# ukmarsbot-line-sensor-basic.net
KiCad netlist of a schematic drawn in EAGLE
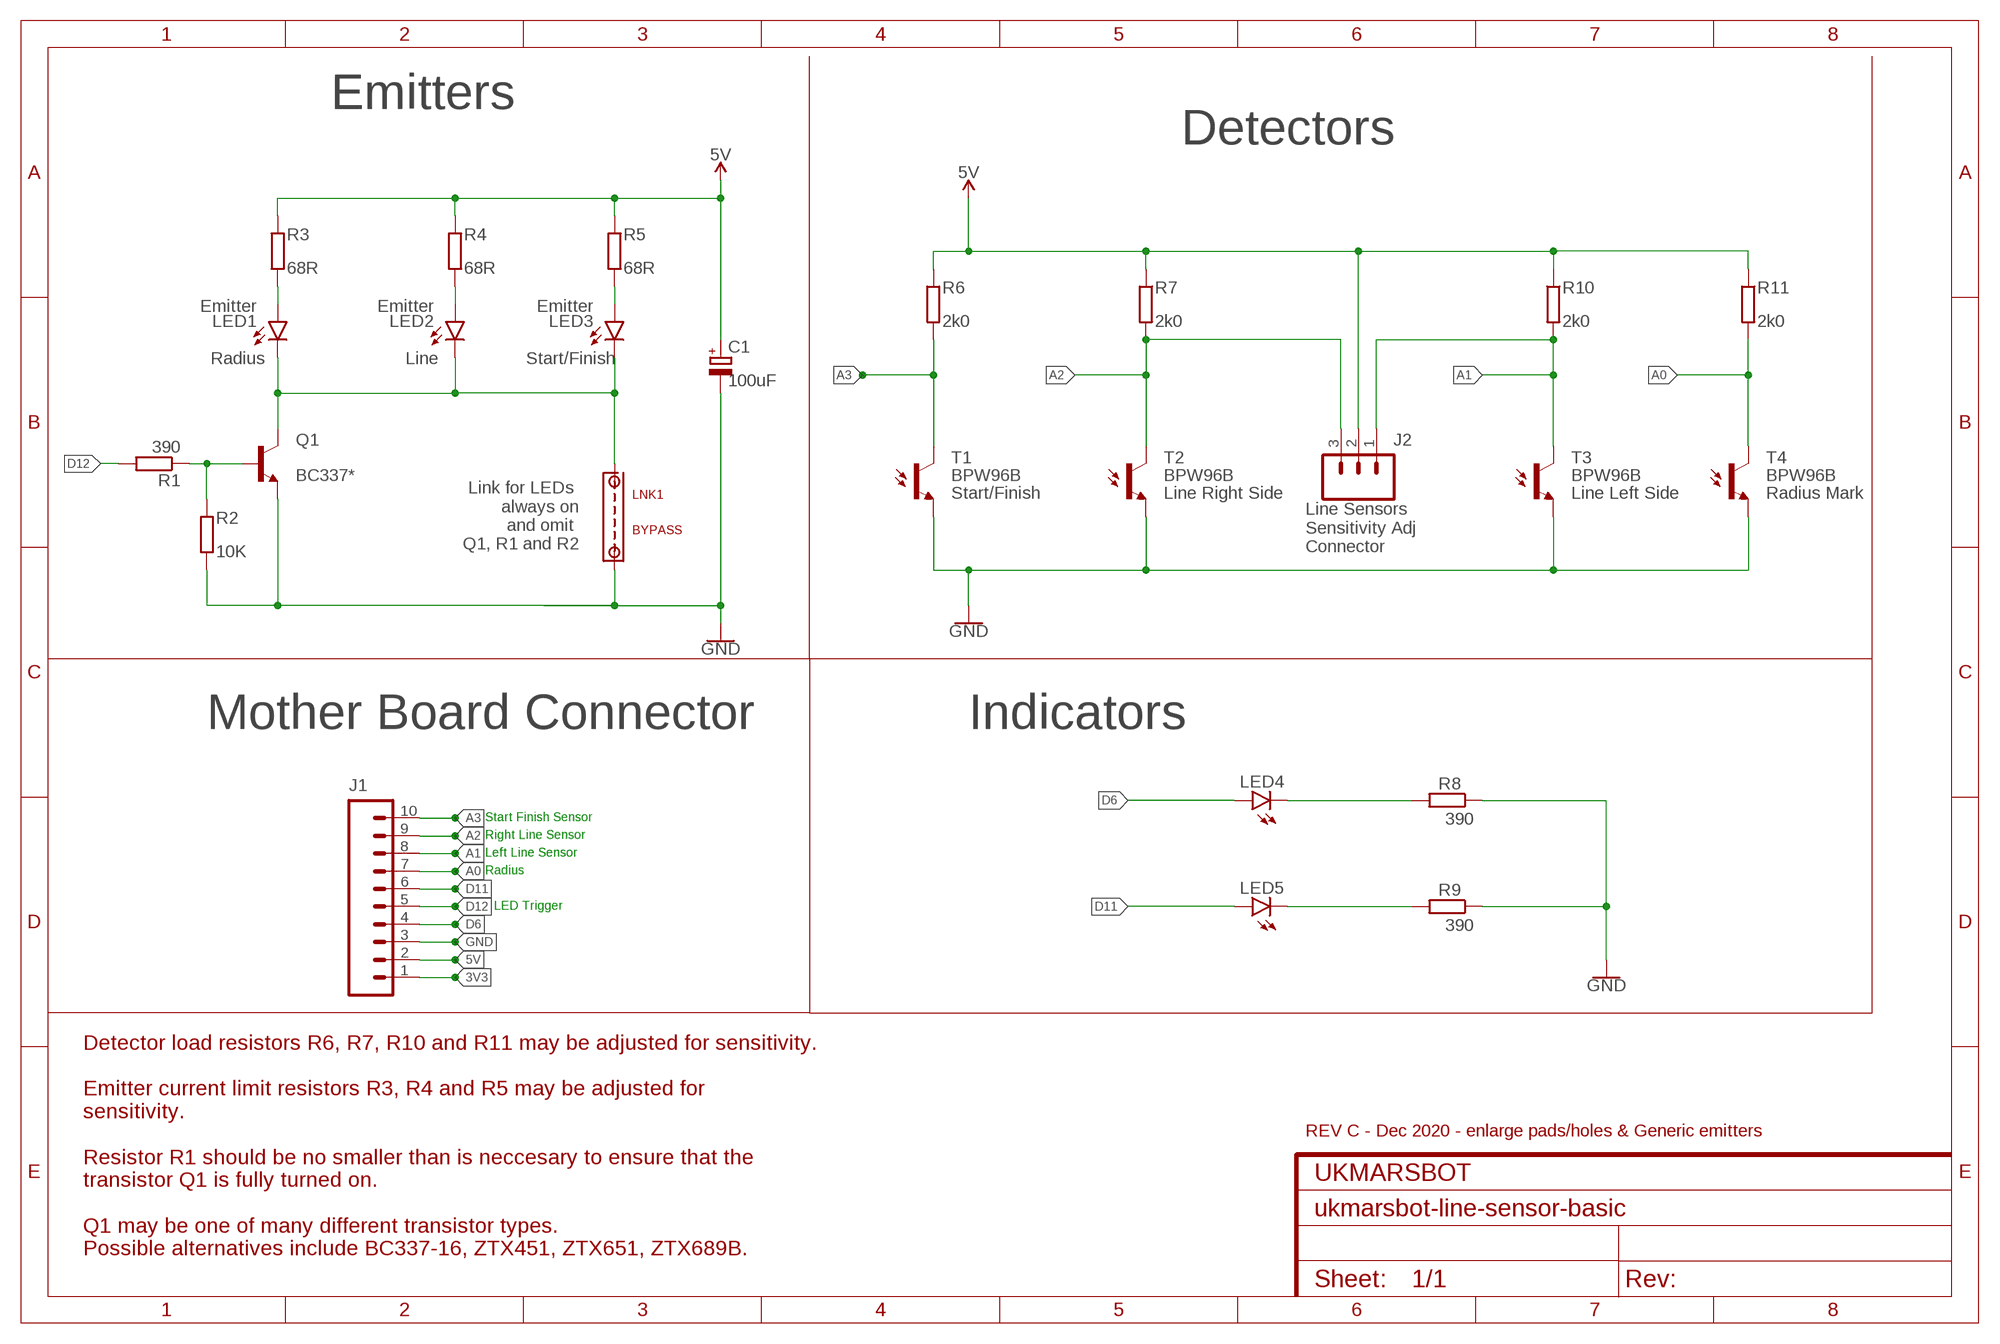
[diagram p0: schematic, sheet 1]

(export (version "E")
  (design (tool "Eeschema 10.0.6"))
  (components
    (comp (ref "C1")
      (value "100uF")
      (footprint "eagle-import:E2,5-7")
      (libsource (lib "eagle-import") (part "CPOL-EUE2.5-7"))
    )
    (comp (ref "J1")
      (value "CONN_10\"")
      (footprint "eagle-import:1X10")
      (libsource (lib "eagle-import") (part "CONN_10{dblquote}"))
    )
    (comp (ref "J2")
      (value "CONN_03")
      (footprint "eagle-import:1X03")
      (libsource (lib "eagle-import") (part "CONN_03"))
    )
    (comp (ref "LED1")
      (value "Emitter")
      (footprint "eagle-import:LED_5MM")
      (libsource (lib "eagle-import") (part "LED5MM"))
    )
    (comp (ref "LED2")
      (value "Emitter")
      (footprint "eagle-import:LED_5MM")
      (libsource (lib "eagle-import") (part "LED5MM"))
    )
    (comp (ref "LED3")
      (value "Emitter")
      (footprint "eagle-import:LED_5MM")
      (libsource (lib "eagle-import") (part "LED5MM"))
    )
    (comp (ref "LED4")
      (value "LED3MM")
      (footprint "eagle-import:LED_3MM")
      (libsource (lib "eagle-import") (part "LED3MM"))
    )
    (comp (ref "LED5")
      (value "LED3MM")
      (footprint "eagle-import:LED_3MM")
      (libsource (lib "eagle-import") (part "LED3MM"))
    )
    (comp (ref "LNK1")
      (value "BYPASS")
      (footprint "eagle-import:LINK-03")
      (libsource (lib "eagle-import") (part "LINK"))
    )
    (comp (ref "Q1")
      (value "BC337*")
      (footprint "eagle-import:TO92-EBC")
      (libsource (lib "eagle-import") (part "TRANS_NPN"))
    )
    (comp (ref "R1")
      (value "390")
      (footprint "eagle-import:0207_7")
      (libsource (lib "eagle-import") (part "R-EU_0207/7"))
    )
    (comp (ref "R2")
      (value "10K")
      (footprint "eagle-import:0207_7")
      (libsource (lib "eagle-import") (part "R-EU_0207/7"))
    )
    (comp (ref "R3")
      (value "68R")
      (footprint "eagle-import:0207_7")
      (libsource (lib "eagle-import") (part "R-EU_0207/7"))
    )
    (comp (ref "R4")
      (value "68R")
      (footprint "eagle-import:0207_7")
      (libsource (lib "eagle-import") (part "R-EU_0207/7"))
    )
    (comp (ref "R5")
      (value "68R")
      (footprint "eagle-import:0207_7")
      (libsource (lib "eagle-import") (part "R-EU_0207/7"))
    )
    (comp (ref "R6")
      (value "2k0")
      (footprint "eagle-import:0207_7")
      (libsource (lib "eagle-import") (part "R-EU_0207/7"))
    )
    (comp (ref "R7")
      (value "2k0")
      (footprint "eagle-import:0207_7")
      (libsource (lib "eagle-import") (part "R-EU_0207/7"))
    )
    (comp (ref "R8")
      (value "390")
      (footprint "eagle-import:0207_7")
      (libsource (lib "eagle-import") (part "R-EU_0207/7"))
    )
    (comp (ref "R9")
      (value "390")
      (footprint "eagle-import:0207_7")
      (libsource (lib "eagle-import") (part "R-EU_0207/7"))
    )
    (comp (ref "R10")
      (value "2k0")
      (footprint "eagle-import:0207_7")
      (libsource (lib "eagle-import") (part "R-EU_0207/7"))
    )
    (comp (ref "R11")
      (value "2k0")
      (footprint "eagle-import:0207_7")
      (libsource (lib "eagle-import") (part "R-EU_0207/7"))
    )
    (comp (ref "T1")
      (value "BPW96B")
      (footprint "eagle-import:PHOTOTRANSISTOR_5MM")
      (libsource (lib "eagle-import") (part "PHOTOTRANSISTOR5MM"))
    )
    (comp (ref "T2")
      (value "BPW96B")
      (footprint "eagle-import:PHOTOTRANSISTOR_5MM")
      (libsource (lib "eagle-import") (part "PHOTOTRANSISTOR5MM"))
    )
    (comp (ref "T3")
      (value "BPW96B")
      (footprint "eagle-import:PHOTOTRANSISTOR_5MM")
      (libsource (lib "eagle-import") (part "PHOTOTRANSISTOR5MM"))
    )
    (comp (ref "T4")
      (value "BPW96B")
      (footprint "eagle-import:PHOTOTRANSISTOR_5MM")
      (libsource (lib "eagle-import") (part "PHOTOTRANSISTOR5MM"))
    )
  )
  (nets
    (net (code "1") (name "3V3") (class "Default")
      (node (ref "J1") (pin "1") (pinfunction "1_1") (pintype "passive"))
    )
    (net (code "2") (name "5V") (class "Default")
      (node (ref "C1") (pin "+") (pinfunction "+_+") (pintype "passive"))
      (node (ref "J1") (pin "2") (pinfunction "2_2") (pintype "passive"))
      (node (ref "J2") (pin "2") (pinfunction "2_2") (pintype "passive"))
      (node (ref "R10") (pin "1") (pinfunction "1_1") (pintype "passive"))
      (node (ref "R11") (pin "1") (pinfunction "1_1") (pintype "passive"))
      (node (ref "R3") (pin "2") (pinfunction "2_2") (pintype "passive"))
      (node (ref "R4") (pin "2") (pinfunction "2_2") (pintype "passive"))
      (node (ref "R5") (pin "2") (pinfunction "2_2") (pintype "passive"))
      (node (ref "R6") (pin "1") (pinfunction "1_1") (pintype "passive"))
      (node (ref "R7") (pin "1") (pinfunction "1_1") (pintype "passive"))
    )
    (net (code "3") (name "A0") (class "Default")
      (node (ref "J1") (pin "7") (pinfunction "7_7") (pintype "passive"))
      (node (ref "R11") (pin "2") (pinfunction "2_2") (pintype "passive"))
      (node (ref "T4") (pin "C") (pinfunction "C_C") (pintype "passive"))
    )
    (net (code "4") (name "A1") (class "Default")
      (node (ref "J1") (pin "8") (pinfunction "8_8") (pintype "passive"))
      (node (ref "J2") (pin "1") (pinfunction "1_1") (pintype "passive"))
      (node (ref "R10") (pin "2") (pinfunction "2_2") (pintype "passive"))
      (node (ref "T3") (pin "C") (pinfunction "C_C") (pintype "passive"))
    )
    (net (code "5") (name "A2") (class "Default")
      (node (ref "J1") (pin "9") (pinfunction "9_9") (pintype "passive"))
      (node (ref "J2") (pin "3") (pinfunction "3_3") (pintype "passive"))
      (node (ref "R7") (pin "2") (pinfunction "2_2") (pintype "passive"))
      (node (ref "T2") (pin "C") (pinfunction "C_C") (pintype "passive"))
    )
    (net (code "6") (name "A3") (class "Default")
      (node (ref "J1") (pin "10") (pinfunction "10_10") (pintype "passive"))
      (node (ref "R6") (pin "2") (pinfunction "2_2") (pintype "passive"))
      (node (ref "T1") (pin "C") (pinfunction "C_C") (pintype "passive"))
    )
    (net (code "7") (name "D6") (class "Default")
      (node (ref "J1") (pin "4") (pinfunction "4_4") (pintype "passive"))
      (node (ref "LED4") (pin "A") (pinfunction "A_A") (pintype "passive"))
    )
    (net (code "8") (name "D11") (class "Default")
      (node (ref "J1") (pin "6") (pinfunction "6_6") (pintype "passive"))
      (node (ref "LED5") (pin "A") (pinfunction "A_A") (pintype "passive"))
    )
    (net (code "9") (name "D12") (class "Default")
      (node (ref "J1") (pin "5") (pinfunction "5_5") (pintype "passive"))
      (node (ref "R1") (pin "2") (pinfunction "2_2") (pintype "passive"))
    )
    (net (code "10") (name "GND") (class "Default")
      (node (ref "C1") (pin "-") (pinfunction "-_-") (pintype "passive"))
      (node (ref "J1") (pin "3") (pinfunction "3_3") (pintype "passive"))
      (node (ref "LNK1") (pin "2") (pinfunction "2_2") (pintype "passive"))
      (node (ref "Q1") (pin "E") (pinfunction "E_E") (pintype "passive"))
      (node (ref "R2") (pin "1") (pinfunction "1_1") (pintype "passive"))
      (node (ref "R8") (pin "1") (pinfunction "1_1") (pintype "passive"))
      (node (ref "R9") (pin "1") (pinfunction "1_1") (pintype "passive"))
      (node (ref "T1") (pin "E") (pinfunction "E_E") (pintype "passive"))
      (node (ref "T2") (pin "E") (pinfunction "E_E") (pintype "passive"))
      (node (ref "T3") (pin "E") (pinfunction "E_E") (pintype "passive"))
      (node (ref "T4") (pin "E") (pinfunction "E_E") (pintype "passive"))
    )
    (net (code "11") (name "Net-(LED1-C)") (class "Default")
      (node (ref "LED1") (pin "K") (pinfunction "C_K") (pintype "passive"))
      (node (ref "LED2") (pin "K") (pinfunction "C_K") (pintype "passive"))
      (node (ref "LED3") (pin "K") (pinfunction "C_K") (pintype "passive"))
      (node (ref "LNK1") (pin "1") (pinfunction "1_1") (pintype "passive"))
      (node (ref "Q1") (pin "C") (pinfunction "C_C") (pintype "passive"))
    )
    (net (code "12") (name "Net-(LED1-PadA)") (class "Default")
      (node (ref "LED1") (pin "A") (pinfunction "A_A") (pintype "passive"))
      (node (ref "R3") (pin "1") (pinfunction "1_1") (pintype "passive"))
    )
    (net (code "13") (name "Net-(LED2-PadA)") (class "Default")
      (node (ref "LED2") (pin "A") (pinfunction "A_A") (pintype "passive"))
      (node (ref "R4") (pin "1") (pinfunction "1_1") (pintype "passive"))
    )
    (net (code "14") (name "Net-(LED3-PadA)") (class "Default")
      (node (ref "LED3") (pin "A") (pinfunction "A_A") (pintype "passive"))
      (node (ref "R5") (pin "1") (pinfunction "1_1") (pintype "passive"))
    )
    (net (code "15") (name "Net-(LED4-C)") (class "Default")
      (node (ref "LED4") (pin "K") (pinfunction "C_K") (pintype "passive"))
      (node (ref "R8") (pin "2") (pinfunction "2_2") (pintype "passive"))
    )
    (net (code "16") (name "Net-(LED5-C)") (class "Default")
      (node (ref "LED5") (pin "K") (pinfunction "C_K") (pintype "passive"))
      (node (ref "R9") (pin "2") (pinfunction "2_2") (pintype "passive"))
    )
    (net (code "17") (name "Net-(Q1-PadB)") (class "Default")
      (node (ref "Q1") (pin "B") (pinfunction "B_B") (pintype "passive"))
      (node (ref "R1") (pin "1") (pinfunction "1_1") (pintype "passive"))
      (node (ref "R2") (pin "2") (pinfunction "2_2") (pintype "passive"))
    )
  )
)
